# newPins-primitive.net
KiCad netlist of a schematic drawn in EAGLE
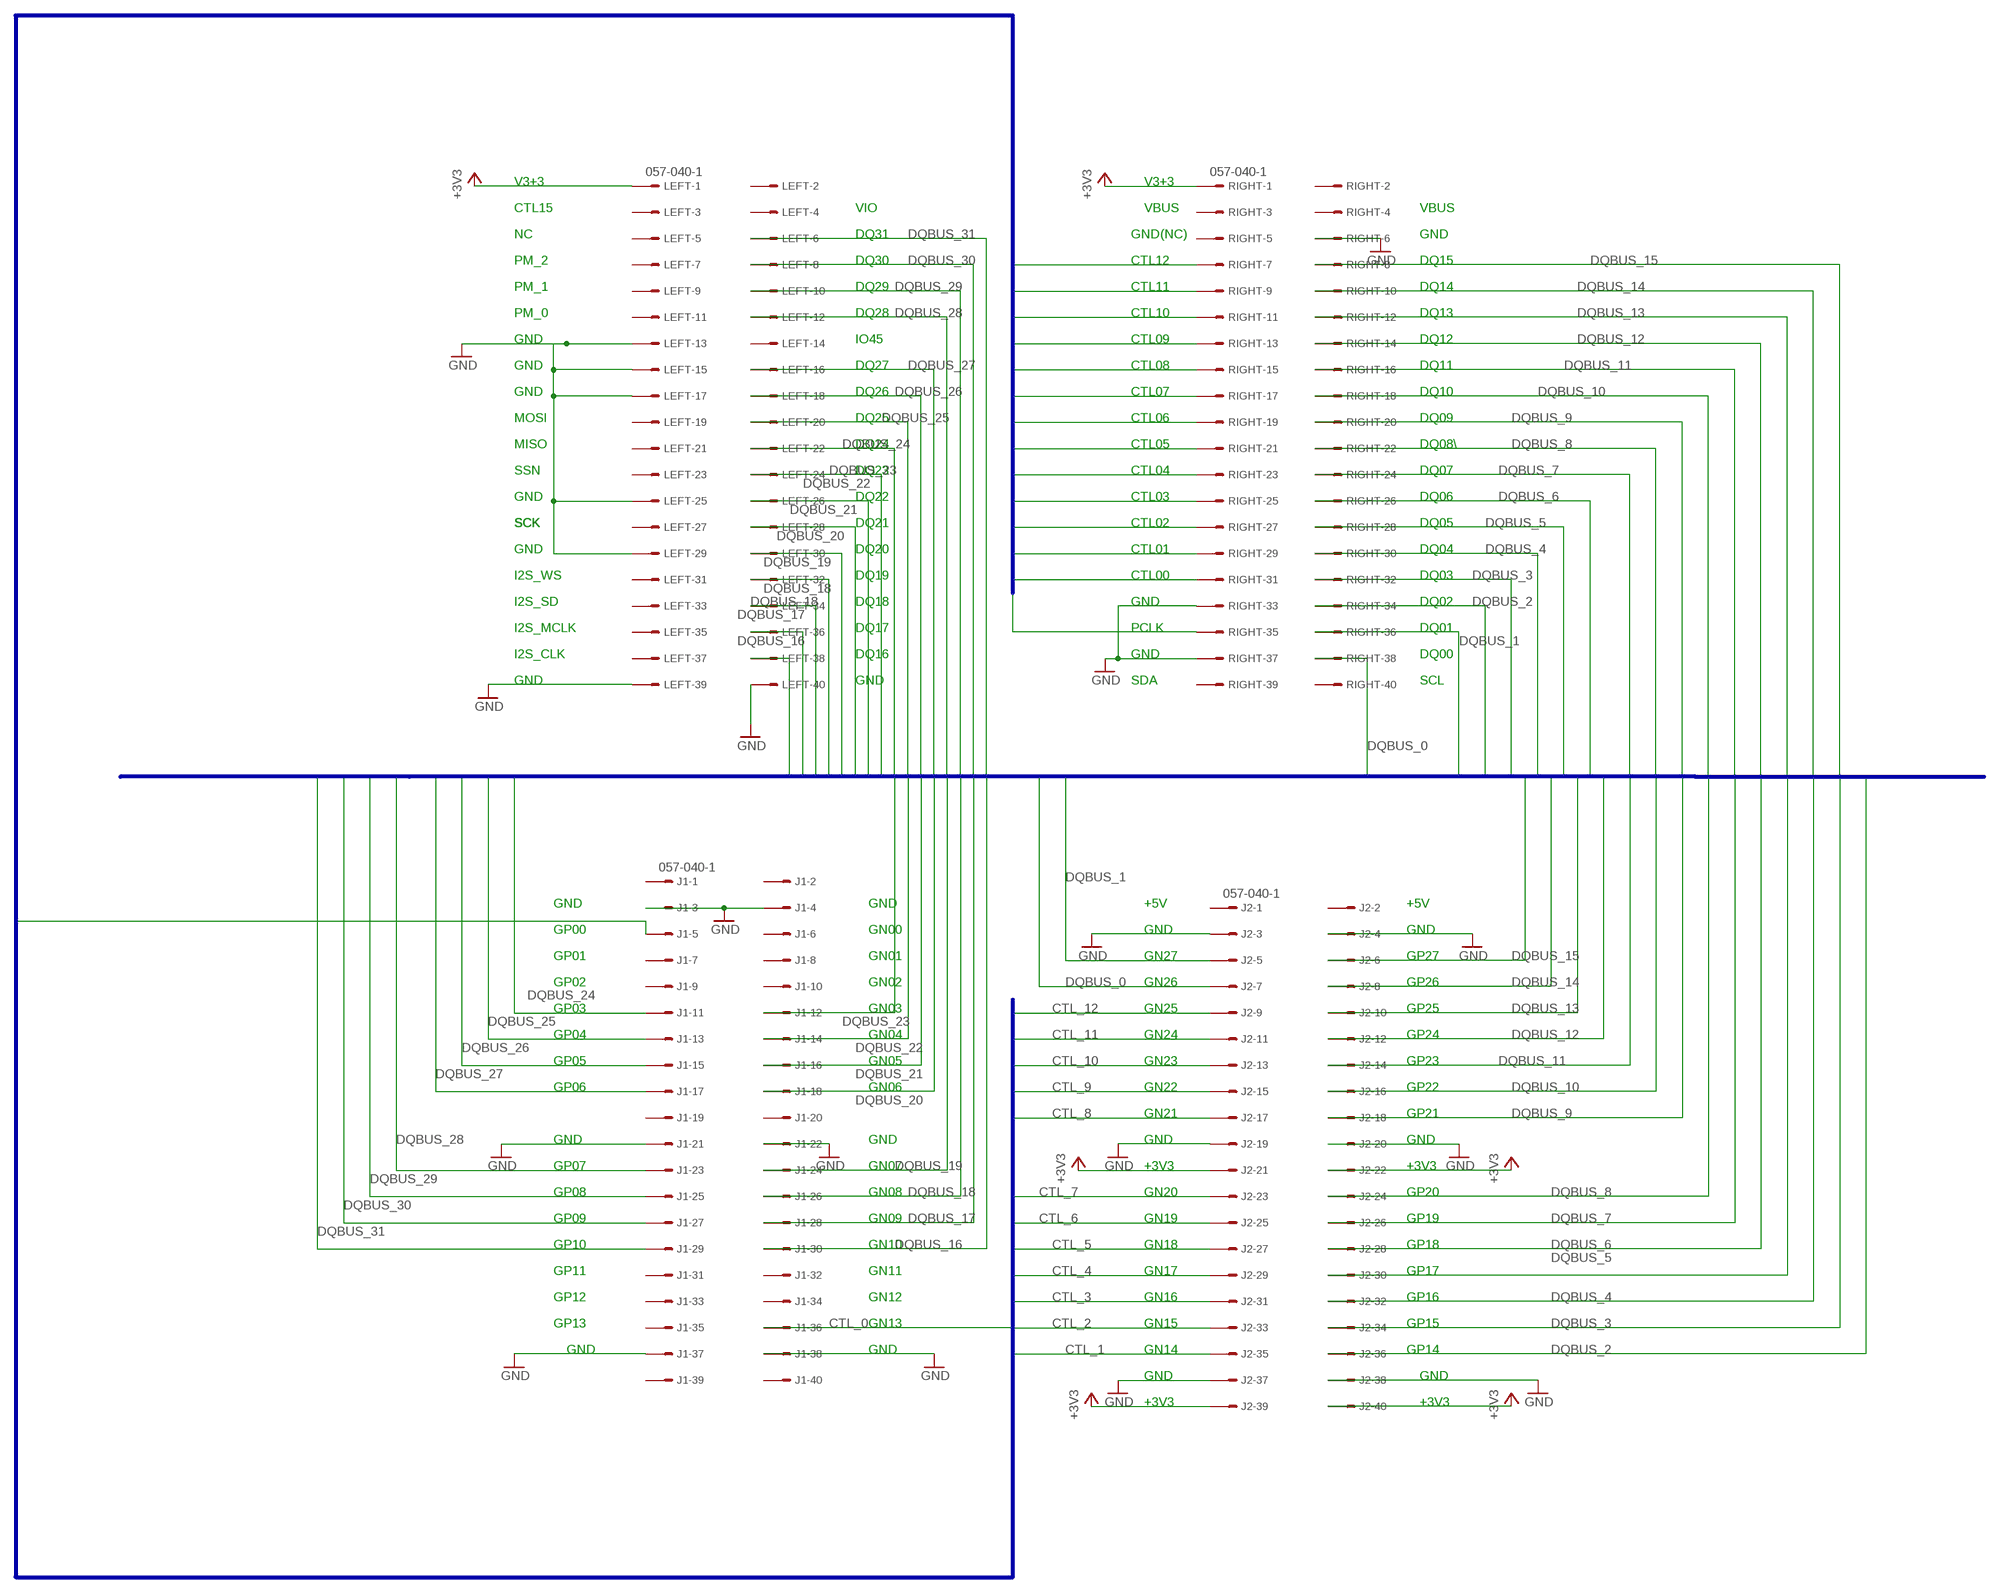
[diagram p0: schematic, sheet 1]

(export (version "E")
  (design (tool "Eeschema 10.0.6"))
  (components
    (comp (ref "J1")
      (value "057-040-1")
      (footprint "eagle-import:057-040-1")
      (libsource (lib "eagle-import") (part "057-040-1"))
    )
    (comp (ref "J2")
      (value "057-040-1")
      (footprint "eagle-import:057-040-1")
      (libsource (lib "eagle-import") (part "057-040-1"))
    )
    (comp (ref "LEFT")
      (value "057-040-1")
      (footprint "eagle-import:057-040-1")
      (libsource (lib "eagle-import") (part "057-040-1"))
    )
    (comp (ref "RIGHT")
      (value "057-040-1")
      (footprint "eagle-import:057-040-1")
      (libsource (lib "eagle-import") (part "057-040-1"))
    )
  )
  (nets
    (net (code "1") (name "+3V3") (class "Default")
      (node (ref "J2") (pin "21") (pinfunction "S_21") (pintype "passive"))
      (node (ref "J2") (pin "22") (pinfunction "S_22") (pintype "passive"))
      (node (ref "J2") (pin "39") (pinfunction "S_39") (pintype "passive"))
      (node (ref "J2") (pin "40") (pinfunction "S_40") (pintype "passive"))
      (node (ref "LEFT") (pin "1") (pinfunction "S_1") (pintype "passive"))
      (node (ref "RIGHT") (pin "1") (pinfunction "S_1") (pintype "passive"))
    )
    (net (code "2") (name "/CTL_0") (class "Default")
      (node (ref "J1") (pin "36") (pinfunction "S_36") (pintype "passive"))
      (node (ref "RIGHT") (pin "31") (pinfunction "S_31") (pintype "passive"))
    )
    (net (code "3") (name "/CTL_1") (class "Default")
      (node (ref "J2") (pin "35") (pinfunction "S_35") (pintype "passive"))
      (node (ref "RIGHT") (pin "29") (pinfunction "S_29") (pintype "passive"))
    )
    (net (code "4") (name "/CTL_2") (class "Default")
      (node (ref "J2") (pin "33") (pinfunction "S_33") (pintype "passive"))
      (node (ref "RIGHT") (pin "27") (pinfunction "S_27") (pintype "passive"))
    )
    (net (code "5") (name "/CTL_3") (class "Default")
      (node (ref "J2") (pin "31") (pinfunction "S_31") (pintype "passive"))
      (node (ref "RIGHT") (pin "25") (pinfunction "S_25") (pintype "passive"))
    )
    (net (code "6") (name "/CTL_4") (class "Default")
      (node (ref "J2") (pin "29") (pinfunction "S_29") (pintype "passive"))
      (node (ref "RIGHT") (pin "23") (pinfunction "S_23") (pintype "passive"))
    )
    (net (code "7") (name "/CTL_5") (class "Default")
      (node (ref "J2") (pin "27") (pinfunction "S_27") (pintype "passive"))
      (node (ref "RIGHT") (pin "21") (pinfunction "S_21") (pintype "passive"))
    )
    (net (code "8") (name "/CTL_6") (class "Default")
      (node (ref "J2") (pin "25") (pinfunction "S_25") (pintype "passive"))
      (node (ref "RIGHT") (pin "19") (pinfunction "S_19") (pintype "passive"))
    )
    (net (code "9") (name "/CTL_7") (class "Default")
      (node (ref "J2") (pin "23") (pinfunction "S_23") (pintype "passive"))
      (node (ref "RIGHT") (pin "17") (pinfunction "S_17") (pintype "passive"))
    )
    (net (code "10") (name "/CTL_8") (class "Default")
      (node (ref "J2") (pin "17") (pinfunction "S_17") (pintype "passive"))
      (node (ref "RIGHT") (pin "15") (pinfunction "S_15") (pintype "passive"))
    )
    (net (code "11") (name "/CTL_9") (class "Default")
      (node (ref "J2") (pin "15") (pinfunction "S_15") (pintype "passive"))
      (node (ref "RIGHT") (pin "13") (pinfunction "S_13") (pintype "passive"))
    )
    (net (code "12") (name "/CTL_10") (class "Default")
      (node (ref "J2") (pin "13") (pinfunction "S_13") (pintype "passive"))
      (node (ref "RIGHT") (pin "11") (pinfunction "S_11") (pintype "passive"))
    )
    (net (code "13") (name "/CTL_11") (class "Default")
      (node (ref "J2") (pin "11") (pinfunction "S_11") (pintype "passive"))
      (node (ref "RIGHT") (pin "9") (pinfunction "S_9") (pintype "passive"))
    )
    (net (code "14") (name "/CTL_12") (class "Default")
      (node (ref "J2") (pin "9") (pinfunction "S_9") (pintype "passive"))
      (node (ref "RIGHT") (pin "7") (pinfunction "S_7") (pintype "passive"))
    )
    (net (code "15") (name "/CTL_PCLK") (class "Default")
      (node (ref "J1") (pin "5") (pinfunction "S_5") (pintype "passive"))
      (node (ref "RIGHT") (pin "35") (pinfunction "S_35") (pintype "passive"))
    )
    (net (code "16") (name "/DQBUS_0") (class "Default")
      (node (ref "J2") (pin "7") (pinfunction "S_7") (pintype "passive"))
      (node (ref "RIGHT") (pin "38") (pinfunction "S_38") (pintype "passive"))
    )
    (net (code "17") (name "/DQBUS_1") (class "Default")
      (node (ref "J2") (pin "5") (pinfunction "S_5") (pintype "passive"))
      (node (ref "RIGHT") (pin "36") (pinfunction "S_36") (pintype "passive"))
    )
    (net (code "18") (name "/DQBUS_2") (class "Default")
      (node (ref "J2") (pin "36") (pinfunction "S_36") (pintype "passive"))
      (node (ref "RIGHT") (pin "34") (pinfunction "S_34") (pintype "passive"))
    )
    (net (code "19") (name "/DQBUS_3") (class "Default")
      (node (ref "J2") (pin "34") (pinfunction "S_34") (pintype "passive"))
      (node (ref "RIGHT") (pin "32") (pinfunction "S_32") (pintype "passive"))
    )
    (net (code "20") (name "/DQBUS_4") (class "Default")
      (node (ref "J2") (pin "32") (pinfunction "S_32") (pintype "passive"))
      (node (ref "RIGHT") (pin "30") (pinfunction "S_30") (pintype "passive"))
    )
    (net (code "21") (name "/DQBUS_5") (class "Default")
      (node (ref "J2") (pin "30") (pinfunction "S_30") (pintype "passive"))
      (node (ref "RIGHT") (pin "28") (pinfunction "S_28") (pintype "passive"))
    )
    (net (code "22") (name "/DQBUS_6") (class "Default")
      (node (ref "J2") (pin "28") (pinfunction "S_28") (pintype "passive"))
      (node (ref "RIGHT") (pin "26") (pinfunction "S_26") (pintype "passive"))
    )
    (net (code "23") (name "/DQBUS_7") (class "Default")
      (node (ref "J2") (pin "26") (pinfunction "S_26") (pintype "passive"))
      (node (ref "RIGHT") (pin "24") (pinfunction "S_24") (pintype "passive"))
    )
    (net (code "24") (name "/DQBUS_8") (class "Default")
      (node (ref "J2") (pin "24") (pinfunction "S_24") (pintype "passive"))
      (node (ref "RIGHT") (pin "22") (pinfunction "S_22") (pintype "passive"))
    )
    (net (code "25") (name "/DQBUS_9") (class "Default")
      (node (ref "J2") (pin "18") (pinfunction "S_18") (pintype "passive"))
      (node (ref "RIGHT") (pin "20") (pinfunction "S_20") (pintype "passive"))
    )
    (net (code "26") (name "/DQBUS_10") (class "Default")
      (node (ref "J2") (pin "16") (pinfunction "S_16") (pintype "passive"))
      (node (ref "RIGHT") (pin "18") (pinfunction "S_18") (pintype "passive"))
    )
    (net (code "27") (name "/DQBUS_11") (class "Default")
      (node (ref "J2") (pin "14") (pinfunction "S_14") (pintype "passive"))
      (node (ref "RIGHT") (pin "16") (pinfunction "S_16") (pintype "passive"))
    )
    (net (code "28") (name "/DQBUS_12") (class "Default")
      (node (ref "J2") (pin "12") (pinfunction "S_12") (pintype "passive"))
      (node (ref "RIGHT") (pin "14") (pinfunction "S_14") (pintype "passive"))
    )
    (net (code "29") (name "/DQBUS_13") (class "Default")
      (node (ref "J2") (pin "10") (pinfunction "S_10") (pintype "passive"))
      (node (ref "RIGHT") (pin "12") (pinfunction "S_12") (pintype "passive"))
    )
    (net (code "30") (name "/DQBUS_14") (class "Default")
      (node (ref "J2") (pin "8") (pinfunction "S_8") (pintype "passive"))
      (node (ref "RIGHT") (pin "10") (pinfunction "S_10") (pintype "passive"))
    )
    (net (code "31") (name "/DQBUS_15") (class "Default")
      (node (ref "J2") (pin "6") (pinfunction "S_6") (pintype "passive"))
      (node (ref "RIGHT") (pin "8") (pinfunction "S_8") (pintype "passive"))
    )
    (net (code "32") (name "/DQBUS_16") (class "Default")
      (node (ref "J1") (pin "30") (pinfunction "S_30") (pintype "passive"))
      (node (ref "LEFT") (pin "38") (pinfunction "S_38") (pintype "passive"))
    )
    (net (code "33") (name "/DQBUS_17") (class "Default")
      (node (ref "J1") (pin "28") (pinfunction "S_28") (pintype "passive"))
      (node (ref "LEFT") (pin "36") (pinfunction "S_36") (pintype "passive"))
    )
    (net (code "34") (name "/DQBUS_18") (class "Default")
      (node (ref "J1") (pin "26") (pinfunction "S_26") (pintype "passive"))
      (node (ref "LEFT") (pin "34") (pinfunction "S_34") (pintype "passive"))
    )
    (net (code "35") (name "/DQBUS_19") (class "Default")
      (node (ref "J1") (pin "24") (pinfunction "S_24") (pintype "passive"))
      (node (ref "LEFT") (pin "32") (pinfunction "S_32") (pintype "passive"))
    )
    (net (code "36") (name "/DQBUS_20") (class "Default")
      (node (ref "J1") (pin "18") (pinfunction "S_18") (pintype "passive"))
      (node (ref "LEFT") (pin "30") (pinfunction "S_30") (pintype "passive"))
    )
    (net (code "37") (name "/DQBUS_21") (class "Default")
      (node (ref "J1") (pin "16") (pinfunction "S_16") (pintype "passive"))
      (node (ref "LEFT") (pin "28") (pinfunction "S_28") (pintype "passive"))
    )
    (net (code "38") (name "/DQBUS_22") (class "Default")
      (node (ref "J1") (pin "14") (pinfunction "S_14") (pintype "passive"))
      (node (ref "LEFT") (pin "26") (pinfunction "S_26") (pintype "passive"))
    )
    (net (code "39") (name "/DQBUS_23") (class "Default")
      (node (ref "J1") (pin "12") (pinfunction "S_12") (pintype "passive"))
      (node (ref "LEFT") (pin "24") (pinfunction "S_24") (pintype "passive"))
    )
    (net (code "40") (name "/DQBUS_24") (class "Default")
      (node (ref "J1") (pin "11") (pinfunction "S_11") (pintype "passive"))
      (node (ref "LEFT") (pin "22") (pinfunction "S_22") (pintype "passive"))
    )
    (net (code "41") (name "/DQBUS_25") (class "Default")
      (node (ref "J1") (pin "13") (pinfunction "S_13") (pintype "passive"))
      (node (ref "LEFT") (pin "20") (pinfunction "S_20") (pintype "passive"))
    )
    (net (code "42") (name "/DQBUS_26") (class "Default")
      (node (ref "J1") (pin "15") (pinfunction "S_15") (pintype "passive"))
      (node (ref "LEFT") (pin "18") (pinfunction "S_18") (pintype "passive"))
    )
    (net (code "43") (name "/DQBUS_27") (class "Default")
      (node (ref "J1") (pin "17") (pinfunction "S_17") (pintype "passive"))
      (node (ref "LEFT") (pin "16") (pinfunction "S_16") (pintype "passive"))
    )
    (net (code "44") (name "/DQBUS_28") (class "Default")
      (node (ref "J1") (pin "23") (pinfunction "S_23") (pintype "passive"))
      (node (ref "LEFT") (pin "12") (pinfunction "S_12") (pintype "passive"))
    )
    (net (code "45") (name "/DQBUS_29") (class "Default")
      (node (ref "J1") (pin "25") (pinfunction "S_25") (pintype "passive"))
      (node (ref "LEFT") (pin "10") (pinfunction "S_10") (pintype "passive"))
    )
    (net (code "46") (name "/DQBUS_30") (class "Default")
      (node (ref "J1") (pin "27") (pinfunction "S_27") (pintype "passive"))
      (node (ref "LEFT") (pin "8") (pinfunction "S_8") (pintype "passive"))
    )
    (net (code "47") (name "/DQBUS_31") (class "Default")
      (node (ref "J1") (pin "29") (pinfunction "S_29") (pintype "passive"))
      (node (ref "LEFT") (pin "6") (pinfunction "S_6") (pintype "passive"))
    )
    (net (code "48") (name "GND") (class "Default")
      (node (ref "J1") (pin "21") (pinfunction "S_21") (pintype "passive"))
      (node (ref "J1") (pin "22") (pinfunction "S_22") (pintype "passive"))
      (node (ref "J1") (pin "3") (pinfunction "S_3") (pintype "passive"))
      (node (ref "J1") (pin "37") (pinfunction "S_37") (pintype "passive"))
      (node (ref "J1") (pin "38") (pinfunction "S_38") (pintype "passive"))
      (node (ref "J1") (pin "4") (pinfunction "S_4") (pintype "passive"))
      (node (ref "J2") (pin "19") (pinfunction "S_19") (pintype "passive"))
      (node (ref "J2") (pin "20") (pinfunction "S_20") (pintype "passive"))
      (node (ref "J2") (pin "3") (pinfunction "S_3") (pintype "passive"))
      (node (ref "J2") (pin "37") (pinfunction "S_37") (pintype "passive"))
      (node (ref "J2") (pin "38") (pinfunction "S_38") (pintype "passive"))
      (node (ref "J2") (pin "4") (pinfunction "S_4") (pintype "passive"))
      (node (ref "LEFT") (pin "13") (pinfunction "S_13") (pintype "passive"))
      (node (ref "LEFT") (pin "15") (pinfunction "S_15") (pintype "passive"))
      (node (ref "LEFT") (pin "17") (pinfunction "S_17") (pintype "passive"))
      (node (ref "LEFT") (pin "25") (pinfunction "S_25") (pintype "passive"))
      (node (ref "LEFT") (pin "29") (pinfunction "S_29") (pintype "passive"))
      (node (ref "LEFT") (pin "39") (pinfunction "S_39") (pintype "passive"))
      (node (ref "LEFT") (pin "40") (pinfunction "S_40") (pintype "passive"))
      (node (ref "RIGHT") (pin "33") (pinfunction "S_33") (pintype "passive"))
      (node (ref "RIGHT") (pin "37") (pinfunction "S_37") (pintype "passive"))
      (node (ref "RIGHT") (pin "6") (pinfunction "S_6") (pintype "passive"))
    )
    (net (code "49") (name "unconnected-(J1A-S-Pad1)") (class "Default")
      (node (ref "J1") (pin "1") (pinfunction "S_1") (pintype "passive"))
    )
    (net (code "50") (name "unconnected-(J1AA-S-Pad33)") (class "Default")
      (node (ref "J1") (pin "33") (pinfunction "S_33") (pintype "passive"))
    )
    (net (code "51") (name "unconnected-(J1AB-S-Pad34)") (class "Default")
      (node (ref "J1") (pin "34") (pinfunction "S_34") (pintype "passive"))
    )
    (net (code "52") (name "unconnected-(J1AC-S-Pad35)") (class "Default")
      (node (ref "J1") (pin "35") (pinfunction "S_35") (pintype "passive"))
    )
    (net (code "53") (name "unconnected-(J1AG-S-Pad39)") (class "Default")
      (node (ref "J1") (pin "39") (pinfunction "S_39") (pintype "passive"))
    )
    (net (code "54") (name "unconnected-(J1AI-S-Pad40)") (class "Default")
      (node (ref "J1") (pin "40") (pinfunction "S_40") (pintype "passive"))
    )
    (net (code "55") (name "unconnected-(J1AK-S-Pad6)") (class "Default")
      (node (ref "J1") (pin "6") (pinfunction "S_6") (pintype "passive"))
    )
    (net (code "56") (name "unconnected-(J1AL-S-Pad7)") (class "Default")
      (node (ref "J1") (pin "7") (pinfunction "S_7") (pintype "passive"))
    )
    (net (code "57") (name "unconnected-(J1AM-S-Pad8)") (class "Default")
      (node (ref "J1") (pin "8") (pinfunction "S_8") (pintype "passive"))
    )
    (net (code "58") (name "unconnected-(J1AN-S-Pad9)") (class "Default")
      (node (ref "J1") (pin "9") (pinfunction "S_9") (pintype "passive"))
    )
    (net (code "59") (name "unconnected-(J1B-S-Pad10)") (class "Default")
      (node (ref "J1") (pin "10") (pinfunction "S_10") (pintype "passive"))
    )
    (net (code "60") (name "unconnected-(J1K-S-Pad19)") (class "Default")
      (node (ref "J1") (pin "19") (pinfunction "S_19") (pintype "passive"))
    )
    (net (code "61") (name "unconnected-(J1L-S-Pad2)") (class "Default")
      (node (ref "J1") (pin "2") (pinfunction "S_2") (pintype "passive"))
    )
    (net (code "62") (name "unconnected-(J1M-S-Pad20)") (class "Default")
      (node (ref "J1") (pin "20") (pinfunction "S_20") (pintype "passive"))
    )
    (net (code "63") (name "unconnected-(J1Y-S-Pad31)") (class "Default")
      (node (ref "J1") (pin "31") (pinfunction "S_31") (pintype "passive"))
    )
    (net (code "64") (name "unconnected-(J1Z-S-Pad32)") (class "Default")
      (node (ref "J1") (pin "32") (pinfunction "S_32") (pintype "passive"))
    )
    (net (code "65") (name "unconnected-(J2A-S-Pad1)") (class "Default")
      (node (ref "J2") (pin "1") (pinfunction "S_1") (pintype "passive"))
    )
    (net (code "66") (name "unconnected-(J2L-S-Pad2)") (class "Default")
      (node (ref "J2") (pin "2") (pinfunction "S_2") (pintype "passive"))
    )
    (net (code "67") (name "unconnected-(LEFTAA-S-Pad33)") (class "Default")
      (node (ref "LEFT") (pin "33") (pinfunction "S_33") (pintype "passive"))
    )
    (net (code "68") (name "unconnected-(LEFTAC-S-Pad35)") (class "Default")
      (node (ref "LEFT") (pin "35") (pinfunction "S_35") (pintype "passive"))
    )
    (net (code "69") (name "unconnected-(LEFTAE-S-Pad37)") (class "Default")
      (node (ref "LEFT") (pin "37") (pinfunction "S_37") (pintype "passive"))
    )
    (net (code "70") (name "unconnected-(LEFTAH-S-Pad4)") (class "Default")
      (node (ref "LEFT") (pin "4") (pinfunction "S_4") (pintype "passive"))
    )
    (net (code "71") (name "unconnected-(LEFTAJ-S-Pad5)") (class "Default")
      (node (ref "LEFT") (pin "5") (pinfunction "S_5") (pintype "passive"))
    )
    (net (code "72") (name "unconnected-(LEFTAL-S-Pad7)") (class "Default")
      (node (ref "LEFT") (pin "7") (pinfunction "S_7") (pintype "passive"))
    )
    (net (code "73") (name "unconnected-(LEFTAN-S-Pad9)") (class "Default")
      (node (ref "LEFT") (pin "9") (pinfunction "S_9") (pintype "passive"))
    )
    (net (code "74") (name "unconnected-(LEFTC-S-Pad11)") (class "Default")
      (node (ref "LEFT") (pin "11") (pinfunction "S_11") (pintype "passive"))
    )
    (net (code "75") (name "unconnected-(LEFTF-S-Pad14)") (class "Default")
      (node (ref "LEFT") (pin "14") (pinfunction "S_14") (pintype "passive"))
    )
    (net (code "76") (name "unconnected-(LEFTK-S-Pad19)") (class "Default")
      (node (ref "LEFT") (pin "19") (pinfunction "S_19") (pintype "passive"))
    )
    (net (code "77") (name "unconnected-(LEFTL-S-Pad2)") (class "Default")
      (node (ref "LEFT") (pin "2") (pinfunction "S_2") (pintype "passive"))
    )
    (net (code "78") (name "unconnected-(LEFTN-S-Pad21)") (class "Default")
      (node (ref "LEFT") (pin "21") (pinfunction "S_21") (pintype "passive"))
    )
    (net (code "79") (name "unconnected-(LEFTP-S-Pad23)") (class "Default")
      (node (ref "LEFT") (pin "23") (pinfunction "S_23") (pintype "passive"))
    )
    (net (code "80") (name "unconnected-(LEFTT-S-Pad27)") (class "Default")
      (node (ref "LEFT") (pin "27") (pinfunction "S_27") (pintype "passive"))
    )
    (net (code "81") (name "unconnected-(LEFTW-S-Pad3)") (class "Default")
      (node (ref "LEFT") (pin "3") (pinfunction "S_3") (pintype "passive"))
    )
    (net (code "82") (name "unconnected-(LEFTY-S-Pad31)") (class "Default")
      (node (ref "LEFT") (pin "31") (pinfunction "S_31") (pintype "passive"))
    )
    (net (code "83") (name "unconnected-(RIGHTAG-S-Pad39)") (class "Default")
      (node (ref "RIGHT") (pin "39") (pinfunction "S_39") (pintype "passive"))
    )
    (net (code "84") (name "unconnected-(RIGHTAH-S-Pad4)") (class "Default")
      (node (ref "RIGHT") (pin "4") (pinfunction "S_4") (pintype "passive"))
    )
    (net (code "85") (name "unconnected-(RIGHTAI-S-Pad40)") (class "Default")
      (node (ref "RIGHT") (pin "40") (pinfunction "S_40") (pintype "passive"))
    )
    (net (code "86") (name "unconnected-(RIGHTAJ-S-Pad5)") (class "Default")
      (node (ref "RIGHT") (pin "5") (pinfunction "S_5") (pintype "passive"))
    )
    (net (code "87") (name "unconnected-(RIGHTL-S-Pad2)") (class "Default")
      (node (ref "RIGHT") (pin "2") (pinfunction "S_2") (pintype "passive"))
    )
    (net (code "88") (name "unconnected-(RIGHTW-S-Pad3)") (class "Default")
      (node (ref "RIGHT") (pin "3") (pinfunction "S_3") (pintype "passive"))
    )
  )
)
